# c_pubsub_lower_isolate_5V.net
KiCad netlist of a schematic drawn in EAGLE
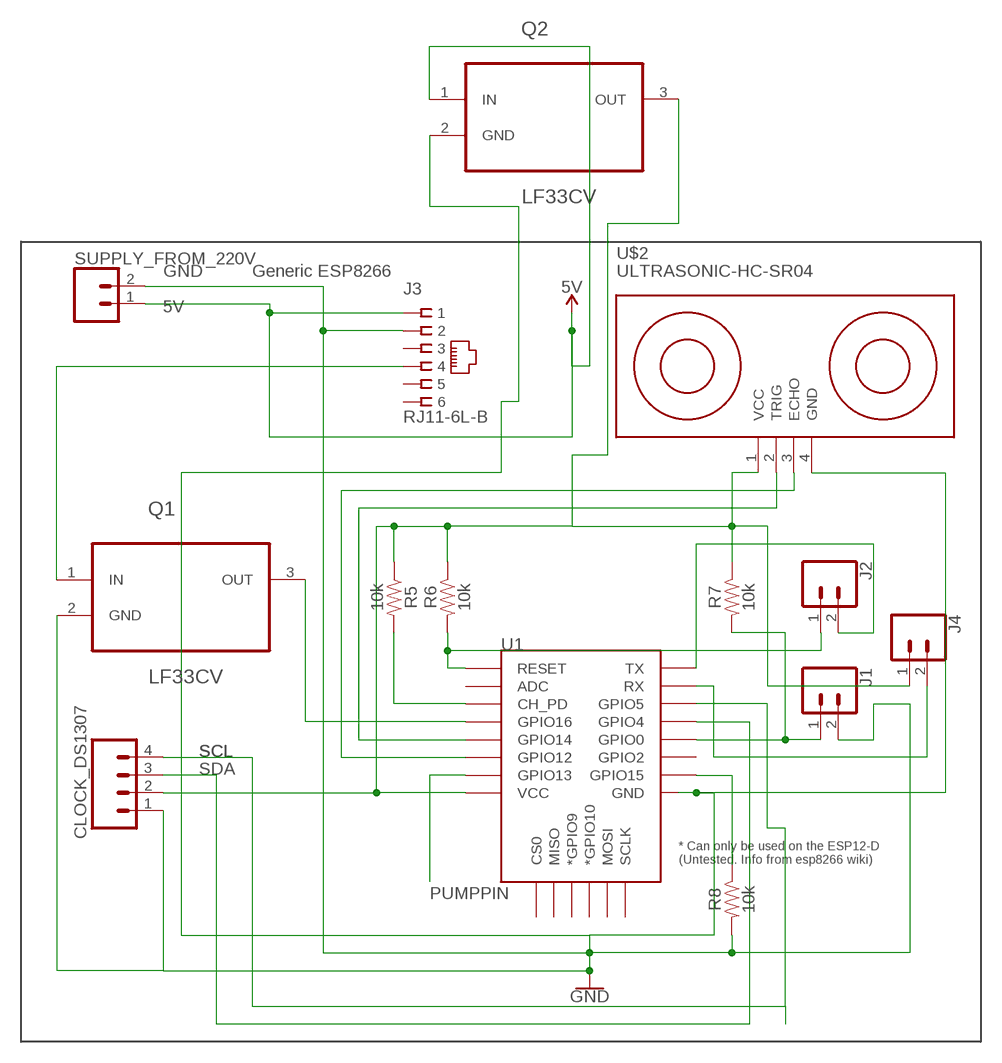
[diagram p0: schematic, sheet 1]

(export (version "E")
  (design (tool "Eeschema 10.0.6"))
  (components
    (comp (ref "CLOCK_DS1307")
      (value "CONN_04PTH")
      (footprint "eagle-import:1X04")
      (libsource (lib "eagle-import") (part "CONN_04PTH"))
    )
    (comp (ref "J1")
      (value "CONN_02")
      (footprint "eagle-import:1X02")
      (libsource (lib "eagle-import") (part "CONN_02"))
    )
    (comp (ref "J2")
      (value "CONN_02")
      (footprint "eagle-import:1X02")
      (libsource (lib "eagle-import") (part "CONN_02"))
    )
    (comp (ref "J3")
      (value "RJ11-6L-B")
      (footprint "eagle-import:RJ11-NO_SHIELD")
      (fields (field (name "MF") "TYCO ELECTRONICS"))
      (libsource (lib "eagle-import") (part "RJ11-6L-B"))
    )
    (comp (ref "J4")
      (value "CONN_02")
      (footprint "eagle-import:1X02")
      (libsource (lib "eagle-import") (part "CONN_02"))
    )
    (comp (ref "Q1")
      (value "LF33CV")
      (footprint "eagle-import:TO254P450X1020X1935-3P")
      (fields (field (name "DIGI-KEY_PART_NUMBER") "497-7313-5-ND") (field (name "MF") "STMicroelectronics"))
      (libsource (lib "eagle-import") (part "LF33CV"))
    )
    (comp (ref "Q2")
      (value "LF33CV")
      (footprint "eagle-import:TO254P450X1020X1935-3P")
      (fields (field (name "DIGI-KEY_PART_NUMBER") "497-7313-5-ND") (field (name "MF") "STMicroelectronics"))
      (libsource (lib "eagle-import") (part "LF33CV"))
    )
    (comp (ref "R5")
      (value "10k")
      (footprint "eagle-import:AXIAL-0.3")
      (libsource (lib "eagle-import") (part "10KOHM-HORIZ-1/4W-1%"))
    )
    (comp (ref "R6")
      (value "10k")
      (footprint "eagle-import:AXIAL-0.3")
      (libsource (lib "eagle-import") (part "10KOHM-HORIZ-1/4W-1%"))
    )
    (comp (ref "R7")
      (value "10k")
      (footprint "eagle-import:AXIAL-0.3")
      (libsource (lib "eagle-import") (part "10KOHM-HORIZ-1/4W-1%"))
    )
    (comp (ref "R8")
      (value "10k")
      (footprint "eagle-import:AXIAL-0.3")
      (libsource (lib "eagle-import") (part "10KOHM-HORIZ-1/4W-1%"))
    )
    (comp (ref "SUPPLY_FROM_220V")
      (value "CONN_02")
      (footprint "eagle-import:1X02")
      (libsource (lib "eagle-import") (part "CONN_02"))
    )
    (comp (ref "U$2")
      (value "ULTRASONIC-HC-SR04")
      (footprint "eagle-import:ULTRASONIC-HC-SR04")
      (libsource (lib "eagle-import") (part "ULTRASONIC-HC-SR04"))
    )
    (comp (ref "U1")
      (value "ESP12ESMD")
      (footprint "eagle-import:ESP12E-SMD")
      (libsource (lib "eagle-import") (part "ESP12ESMD"))
    )
  )
  (nets
    (net (code "1") (name "/PUMPPIN") (class "Default")
      (node (ref "U1") (pin "GPIO13") (pinfunction "GPIO13_GPIO13") (pintype "bidirectional"))
    )
    (net (code "2") (name "/SCL") (class "Default")
      (node (ref "CLOCK_DS1307") (pin "4") (pinfunction "4_4") (pintype "passive"))
      (node (ref "U1") (pin "GPIO5") (pinfunction "GPIO5_GPIO5") (pintype "bidirectional"))
    )
    (net (code "3") (name "/SDA") (class "Default")
      (node (ref "CLOCK_DS1307") (pin "3") (pinfunction "3_3") (pintype "passive"))
      (node (ref "U1") (pin "GPIO4") (pinfunction "GPIO4_GPIO4") (pintype "bidirectional"))
    )
    (net (code "4") (name "5V") (class "Default")
      (node (ref "J3") (pin "1") (pinfunction "1_1") (pintype "passive"))
      (node (ref "Q2") (pin "1") (pinfunction "IN_1") (pintype "input"))
      (node (ref "SUPPLY_FROM_220V") (pin "1") (pinfunction "1_1") (pintype "passive"))
    )
    (net (code "5") (name "GND") (class "Default")
      (node (ref "CLOCK_DS1307") (pin "1") (pinfunction "1_1") (pintype "passive"))
      (node (ref "J1") (pin "2") (pinfunction "2_2") (pintype "passive"))
      (node (ref "J3") (pin "2") (pinfunction "2_2") (pintype "passive"))
      (node (ref "Q1") (pin "2") (pinfunction "GND_2") (pintype "passive"))
      (node (ref "Q2") (pin "2") (pinfunction "GND_2") (pintype "passive"))
      (node (ref "R8") (pin "P$2") (pinfunction "2_P$2") (pintype "passive"))
      (node (ref "SUPPLY_FROM_220V") (pin "2") (pinfunction "2_2") (pintype "passive"))
      (node (ref "U$2") (pin "4") (pinfunction "GND_4") (pintype "power_in"))
      (node (ref "U1") (pin "GND") (pinfunction "GND_GND") (pintype "bidirectional"))
    )
    (net (code "6") (name "Net-(Q1-IN)") (class "Default")
      (node (ref "J3") (pin "4") (pinfunction "4_4") (pintype "passive"))
      (node (ref "Q1") (pin "1") (pinfunction "IN_1") (pintype "input"))
    )
    (net (code "7") (name "Net-(Q1-OUT)") (class "Default")
      (node (ref "Q1") (pin "3") (pinfunction "OUT_3") (pintype "output"))
      (node (ref "U1") (pin "GPIO16") (pinfunction "GPIO16_GPIO16") (pintype "bidirectional"))
    )
    (net (code "8") (name "Net-(Q2-OUT)") (class "Default")
      (node (ref "CLOCK_DS1307") (pin "2") (pinfunction "2_2") (pintype "passive"))
      (node (ref "J4") (pin "1") (pinfunction "1_1") (pintype "passive"))
      (node (ref "Q2") (pin "3") (pinfunction "OUT_3") (pintype "output"))
      (node (ref "R5") (pin "P$1") (pinfunction "1_P$1") (pintype "passive"))
      (node (ref "R6") (pin "P$1") (pinfunction "1_P$1") (pintype "passive"))
      (node (ref "R7") (pin "P$1") (pinfunction "1_P$1") (pintype "passive"))
      (node (ref "U$2") (pin "1") (pinfunction "VCC_1") (pintype "power_in"))
      (node (ref "U1") (pin "VCC") (pinfunction "VCC_VCC") (pintype "bidirectional"))
    )
    (net (code "9") (name "Net-(R5-2)") (class "Default")
      (node (ref "R5") (pin "P$2") (pinfunction "2_P$2") (pintype "passive"))
      (node (ref "U1") (pin "CH_PD") (pinfunction "CH_PD_CH_PD") (pintype "bidirectional"))
    )
    (net (code "10") (name "Net-(R6-2)") (class "Default")
      (node (ref "J2") (pin "1") (pinfunction "1_1") (pintype "passive"))
      (node (ref "R6") (pin "P$2") (pinfunction "2_P$2") (pintype "passive"))
      (node (ref "U1") (pin "RESET") (pinfunction "RESET_RESET") (pintype "bidirectional"))
    )
    (net (code "11") (name "Net-(R7-2)") (class "Default")
      (node (ref "J1") (pin "1") (pinfunction "1_1") (pintype "passive"))
      (node (ref "R7") (pin "P$2") (pinfunction "2_P$2") (pintype "passive"))
      (node (ref "U1") (pin "GPIO0") (pinfunction "GPIO0_GPIO0") (pintype "bidirectional"))
    )
    (net (code "12") (name "Net-(R8-1)") (class "Default")
      (node (ref "R8") (pin "P$1") (pinfunction "1_P$1") (pintype "passive"))
      (node (ref "U1") (pin "GPIO15") (pinfunction "GPIO15_GPIO15") (pintype "bidirectional"))
    )
    (net (code "13") (name "Net-(U$2-ECHO)") (class "Default")
      (node (ref "U$2") (pin "3") (pinfunction "ECHO_3") (pintype "output"))
      (node (ref "U1") (pin "GPIO12") (pinfunction "GPIO12_GPIO12") (pintype "bidirectional"))
    )
    (net (code "14") (name "Net-(U$2-TRIG)") (class "Default")
      (node (ref "U$2") (pin "2") (pinfunction "TRIG_2") (pintype "input"))
      (node (ref "U1") (pin "GPIO14") (pinfunction "GPIO14_GPIO14") (pintype "bidirectional"))
    )
    (net (code "15") (name "Net-(U1-RX)") (class "Default")
      (node (ref "J4") (pin "2") (pinfunction "2_2") (pintype "passive"))
      (node (ref "U1") (pin "RXD0") (pinfunction "RX_RXD0") (pintype "bidirectional"))
    )
    (net (code "16") (name "Net-(U1-TX)") (class "Default")
      (node (ref "J2") (pin "2") (pinfunction "2_2") (pintype "passive"))
      (node (ref "U1") (pin "TXD0") (pinfunction "TX_TXD0") (pintype "bidirectional"))
    )
    (net (code "17") (name "unconnected-(J3-Pad3)") (class "Default")
      (node (ref "J3") (pin "3") (pinfunction "3_3") (pintype "passive"))
    )
    (net (code "18") (name "unconnected-(J3-Pad5)") (class "Default")
      (node (ref "J3") (pin "5") (pinfunction "5_5") (pintype "passive"))
    )
    (net (code "19") (name "unconnected-(J3-Pad6)") (class "Default")
      (node (ref "J3") (pin "6") (pinfunction "6_6") (pintype "passive"))
    )
    (net (code "20") (name "unconnected-(U1-*GPIO9-PadGPIO9)") (class "Default")
      (node (ref "U1") (pin "GPIO9") (pinfunction "*GPIO9_GPIO9") (pintype "bidirectional"))
    )
    (net (code "21") (name "unconnected-(U1-*GPIO10-PadGPIO10)") (class "Default")
      (node (ref "U1") (pin "GPIO10") (pinfunction "*GPIO10_GPIO10") (pintype "bidirectional"))
    )
    (net (code "22") (name "unconnected-(U1-PadADC)") (class "Default")
      (node (ref "U1") (pin "ADC") (pinfunction "ADC_ADC") (pintype "bidirectional"))
    )
    (net (code "23") (name "unconnected-(U1-PadCS0)") (class "Default")
      (node (ref "U1") (pin "CS0") (pinfunction "CS0_CS0") (pintype "bidirectional"))
    )
    (net (code "24") (name "unconnected-(U1-PadGPIO2)") (class "Default")
      (node (ref "U1") (pin "GPIO2") (pinfunction "GPIO2_GPIO2") (pintype "bidirectional"))
    )
    (net (code "25") (name "unconnected-(U1-PadMISO)") (class "Default")
      (node (ref "U1") (pin "MISO") (pinfunction "MISO_MISO") (pintype "bidirectional"))
    )
    (net (code "26") (name "unconnected-(U1-PadMOSI)") (class "Default")
      (node (ref "U1") (pin "MOSI") (pinfunction "MOSI_MOSI") (pintype "bidirectional"))
    )
    (net (code "27") (name "unconnected-(U1-PadSCLK)") (class "Default")
      (node (ref "U1") (pin "SCLK") (pinfunction "SCLK_SCLK") (pintype "bidirectional"))
    )
  )
)
